# Power_Circuit.net
KiCad netlist of a schematic drawn in Altium Designer
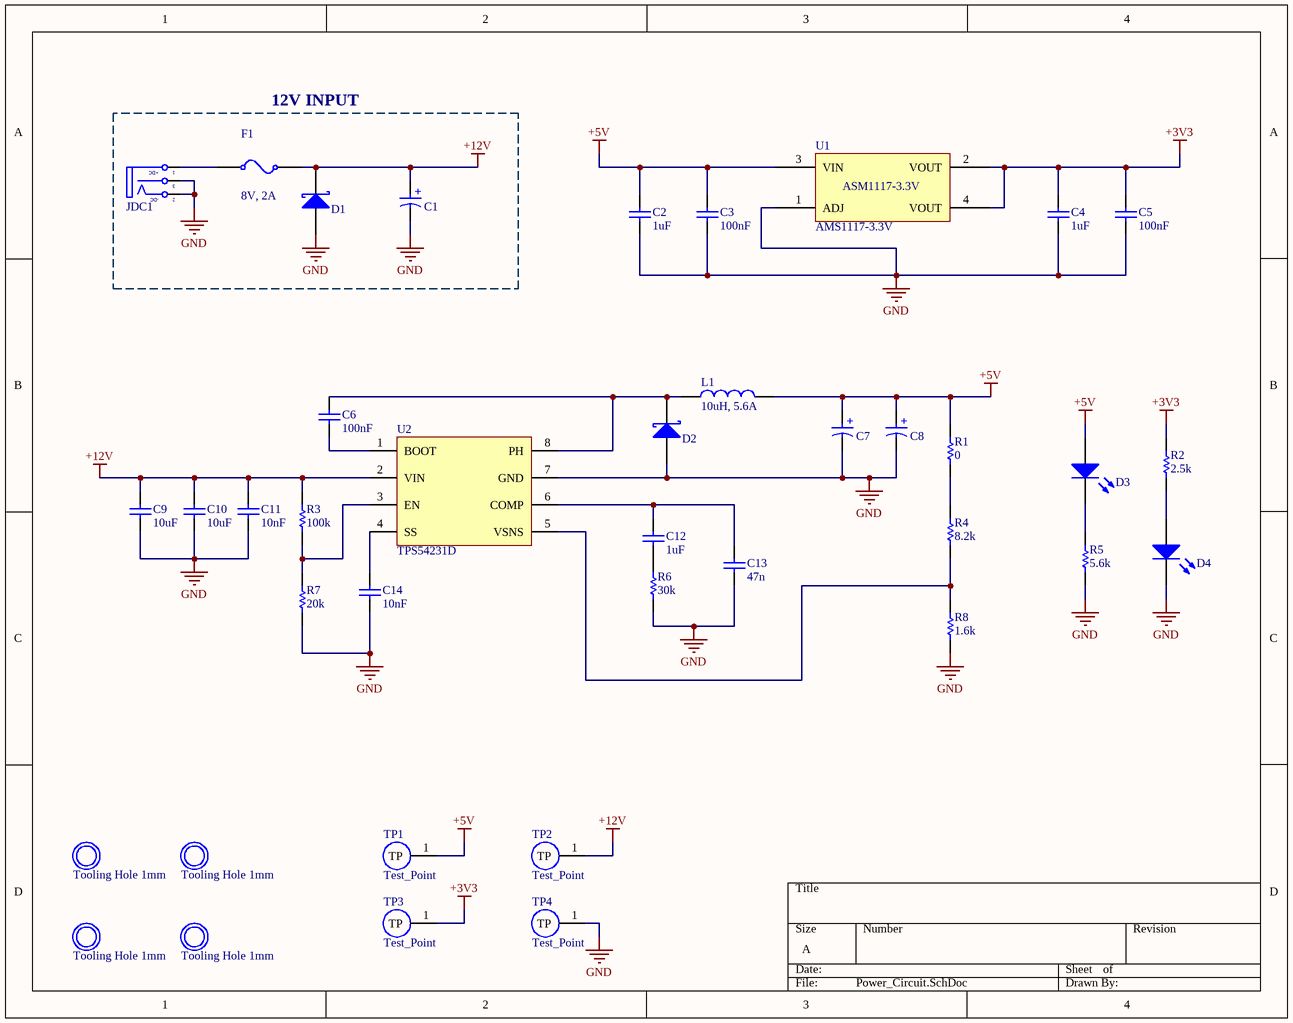
[diagram p0: Power_Circuit.SchDoc]

(export (version "E")
  (design (tool "Eeschema 10.0.6"))
  (components
    (comp (ref "C1")
      (value "47uF")
      (footprint "WCAP-ASLI_D4H5.5")
      (description "V-Chip, D4 x H5.5mm, 22uF, 16V")
      (libsource (lib "SMIOT_Lib_Schematic") (part "865080340003"))
    )
    (comp (ref "C2")
      (value "1uF")
      (footprint "CAP_0603")
      (description "CAP, size 0603, 1uF")
      (libsource (lib "SMIOT_Lib_Schematic") (part "01060310510"))
    )
    (comp (ref "C3")
      (value "100nF")
      (footprint "CAP_0603")
      (description "CAP, size 0603, 100nF")
      (libsource (lib "SMIOT_Lib_Schematic") (part "01060310410"))
    )
    (comp (ref "C4")
      (value "1uF")
      (footprint "CAP_0603")
      (description "CAP, size 0603, 1uF")
      (libsource (lib "SMIOT_Lib_Schematic") (part "01060310510"))
    )
    (comp (ref "C5")
      (value "100nF")
      (footprint "CAP_0603")
      (description "CAP, size 0603, 100nF")
      (libsource (lib "SMIOT_Lib_Schematic") (part "01060310410"))
    )
    (comp (ref "C6")
      (value "100nF")
      (footprint "CAP_0603")
      (description "CAP, size 0603, 100nF")
      (libsource (lib "SMIOT_Lib_Schematic") (part "01060310410"))
    )
    (comp (ref "C7")
      (value "47uF")
      (footprint "WCAP-ASLI_D5H5.5")
      (description "V-Chip, D5 x H5.5mm, 47uF, 16V")
      (libsource (lib "SMIOT_Lib_Schematic") (part "865080342006"))
    )
    (comp (ref "C8")
      (value "47uF")
      (footprint "WCAP-ASLI_D5H5.5")
      (description "V-Chip, D5 x H5.5mm, 47uF, 16V")
      (libsource (lib "SMIOT_Lib_Schematic") (part "865080342006"))
    )
    (comp (ref "C9")
      (value "10uF")
      (footprint "CAP_0603")
      (description "CAP, size 0603,10uF")
      (libsource (lib "SMIOT_Lib_Schematic") (part "01060310010"))
    )
    (comp (ref "C10")
      (value "10uF")
      (footprint "CAP_0603")
      (description "CAP, size 0603,10uF")
      (libsource (lib "SMIOT_Lib_Schematic") (part "01060310010"))
    )
    (comp (ref "C11")
      (value "10nF")
      (footprint "CAP_0603")
      (description "CAP, size 0603, 10nF")
      (libsource (lib "SMIOT_Lib_Schematic") (part "01060310310"))
    )
    (comp (ref "C12")
      (value "1uF")
      (footprint "CAP_0603")
      (description "CAP, size 0603, 1uF")
      (libsource (lib "SMIOT_Lib_Schematic") (part "01060310510"))
    )
    (comp (ref "C13")
      (value "47n")
      (footprint "CAP_0603")
      (description "CAP, size 0603, 47nF")
      (libsource (lib "SMIOT_Lib_Schematic") (part "01060347310"))
    )
    (comp (ref "C14")
      (value "10nF")
      (footprint "CAP_0603")
      (description "CAP, size 0603, 10nF")
      (libsource (lib "SMIOT_Lib_Schematic") (part "01060310310"))
    )
    (comp (ref "D1")
      (value "D Schottky")
      (footprint "SS34")
      (description "Schottky Diode")
      (fields (field (name "PUBLISHER") "Altium Limited"))
      (libsource (lib "Board_C24") (part "D Schottky"))
    )
    (comp (ref "D2")
      (value "D Schottky")
      (footprint "SS34")
      (description "Schottky Diode")
      (fields (field (name "PUBLISHER") "Altium Limited"))
      (libsource (lib "SMIOT_Lib_Schematic") (part "D Schottky"))
    )
    (comp (ref "D3")
      (value "LED SMD")
      (footprint "LED_0805_Blue")
      (description "LED")
      (libsource (lib "SMIOT_Lib_Schematic") (part "LED SMD"))
    )
    (comp (ref "D4")
      (value "LED SMD")
      (footprint "LED_0805_Blue")
      (description "LED")
      (libsource (lib "SMIOT_Lib_Schematic") (part "LED SMD"))
    )
    (comp (ref "F1")
      (value "8V, 2A")
      (footprint "Fuse_SMD_1812")
      (description "Resettable Fuse, Size 1812, 8V, 2A")
      (fields (field (name "MANUFACTURER") "Littelfuse"))
      (libsource (lib "SMIOT_Lib_Schematic") (part "061812200008"))
    )
    (comp (ref "H1")
      (value "Tooling Hole 1mm")
      (footprint "2mm")
      (libsource (lib "SMIOT_Lib_Schematic") (part "Tooling Hole 2mm"))
    )
    (comp (ref "H2")
      (value "Tooling Hole 1mm")
      (footprint "2mm")
      (libsource (lib "SMIOT_Lib_Schematic") (part "Tooling Hole 2mm"))
    )
    (comp (ref "H3")
      (value "Tooling Hole 1mm")
      (footprint "2mm")
      (libsource (lib "SMIOT_Lib_Schematic") (part "Tooling Hole 2mm"))
    )
    (comp (ref "H4")
      (value "Tooling Hole 1mm")
      (footprint "2mm")
      (libsource (lib "SMIOT_Lib_Schematic") (part "Tooling Hole 2mm"))
    )
    (comp (ref "JDC1")
      (value "Jack DC")
      (footprint "DC-IN")
      (description "Jack DC input")
      (libsource (lib "SMIOT_Lib_Schematic") (part "Jack DC"))
    )
    (comp (ref "L1")
      (value "10uH, 5.6A")
      (footprint "WE-PD2A_5848")
      (description "WE-PD2A SMT Power Inductor, size 5848, 10uH, 2.2A")
      (fields
        (field (name "MANUFACTURER PART NUMBER") "78477410")
        (field (name "MANUFACTURER") "Wurth Elektronik")
      )
      (libsource (lib "SMIOT_Lib_Schematic") (part "78477410"))
    )
    (comp (ref "R1")
      (value "0")
      (footprint "resistor_0603")
      (description "RES, 0 Ohm, size 0603, 1%")
      (libsource (lib "SMIOT_Lib_Schematic") (part "0006030001"))
    )
    (comp (ref "R2")
      (value "2.5k")
      (footprint "resistor_0603")
      (description "RES, 2.5K Ohm, size 0603, 5%")
      (libsource (lib "SMIOT_Lib_Schematic") (part "0006032525"))
    )
    (comp (ref "R3")
      (value "100k")
      (footprint "resistor_0603")
      (description "RES, 100k Ohm, size 0603, 1%")
      (libsource (lib "SMIOT_Lib_Schematic") (part "0006031041"))
    )
    (comp (ref "R4")
      (value "8.2k")
      (footprint "resistor_0603")
      (description "RES, 8.2 kOhms, size 0603, 1%")
      (libsource (lib "SMIOT_Lib_Schematic") (part "0006038251"))
    )
    (comp (ref "R5")
      (value "5.6k")
      (footprint "resistor_0603")
      (description "RES, 5.6k Ohm, size 0603, 1%")
      (libsource (lib "SMIOT_Lib_Schematic") (part "0006035621"))
    )
    (comp (ref "R6")
      (value "30k")
      (footprint "resistor_0603")
      (description "RES, 30k Ohm, size 0603, 1%")
      (libsource (lib "SMIOT_Lib_Schematic") (part "0006033205"))
    )
    (comp (ref "R7")
      (value "20k")
      (footprint "resistor_0603")
      (description "RES, 20 kOhms, size 0603, 1%")
      (libsource (lib "SMIOT_Lib_Schematic") (part "0006032031"))
    )
    (comp (ref "R8")
      (value "1.6k")
      (footprint "resistor_0603")
      (description "RES, 1.5 kOhms, size 0603, 1%")
      (libsource (lib "SMIOT_Lib_Schematic") (part "0006031521"))
    )
    (comp (ref "TP1")
      (value "Test_Point")
      (footprint "TP_2MM")
      (description "Test point, 2mm radius")
      (libsource (lib "SMIOT_Lib_Schematic") (part "Test_Point"))
    )
    (comp (ref "TP2")
      (value "Test_Point")
      (footprint "TP_2MM")
      (description "Test point, 2mm radius")
      (libsource (lib "SMIOT_Lib_Schematic") (part "Test_Point"))
    )
    (comp (ref "TP3")
      (value "Test_Point")
      (footprint "TP_2MM")
      (description "Test point, 2mm radius")
      (libsource (lib "SMIOT_Lib_Schematic") (part "Test_Point"))
    )
    (comp (ref "TP4")
      (value "Test_Point")
      (footprint "TP_2MM")
      (description "Test point, 2mm radius")
      (libsource (lib "SMIOT_Lib_Schematic") (part "Test_Point"))
    )
    (comp (ref "U1")
      (value "AMS1117-3.3V")
      (footprint "AMS1117-3.3V SOT223")
      (description "AMS1117-3.3V, OUT 3.3V 1A.")
      (fields (field (name "MANUFACTURER") "AMS"))
      (libsource (lib "SMIOT_Lib_Schematic") (part "AMS1117-3.3V"))
    )
    (comp (ref "U2")
      (value "TPS54231D")
      (footprint "SOIC8")
      (description "Buck Switching Regulator IC Positive Adjustable 0.8V 1 Output 2A 8-SOIC (0.154\", 3.90mm Width)")
      (fields (field (name "MFR") "Texas Instruments"))
      (libsource (lib "SMIOT_Lib_Schematic") (part "TPS54231"))
    )
  )
  (nets
    (net (code "1") (name "+3V3") (class "Default")
      (node (ref "C4") (pin "2") (pinfunction "2_2") (pintype "passive"))
      (node (ref "C5") (pin "2") (pinfunction "2_2") (pintype "passive"))
      (node (ref "R2") (pin "2") (pinfunction "2_2") (pintype "passive"))
      (node (ref "TP3") (pin "1") (pinfunction "TP_1") (pintype "passive"))
      (node (ref "U1") (pin "2") (pinfunction "VOUT_2") (pintype "passive"))
      (node (ref "U1") (pin "4") (pinfunction "VOUT_4") (pintype "power_in"))
    )
    (net (code "2") (name "+5V") (class "Default")
      (node (ref "C2") (pin "2") (pinfunction "2_2") (pintype "passive"))
      (node (ref "C3") (pin "2") (pinfunction "2_2") (pintype "passive"))
      (node (ref "C7") (pin "1") (pinfunction "P_1") (pintype "passive"))
      (node (ref "C8") (pin "1") (pinfunction "P_1") (pintype "passive"))
      (node (ref "D3") (pin "1") (pinfunction "A_1") (pintype "passive"))
      (node (ref "L1") (pin "2") (pinfunction "2_2") (pintype "passive"))
      (node (ref "R1") (pin "2") (pinfunction "2_2") (pintype "passive"))
      (node (ref "TP1") (pin "1") (pinfunction "TP_1") (pintype "passive"))
      (node (ref "U1") (pin "3") (pinfunction "VIN_3") (pintype "passive"))
    )
    (net (code "3") (name "+12V") (class "Default")
      (node (ref "C1") (pin "1") (pinfunction "P_1") (pintype "passive"))
      (node (ref "C10") (pin "2") (pinfunction "2_2") (pintype "passive"))
      (node (ref "C11") (pin "2") (pinfunction "2_2") (pintype "passive"))
      (node (ref "C9") (pin "2") (pinfunction "2_2") (pintype "passive"))
      (node (ref "D1") (pin "2") (pinfunction "K_2") (pintype "passive"))
      (node (ref "F1") (pin "1") (pinfunction "1_1") (pintype "passive"))
      (node (ref "R3") (pin "2") (pinfunction "2_2") (pintype "passive"))
      (node (ref "TP2") (pin "1") (pinfunction "TP_1") (pintype "passive"))
      (node (ref "U2") (pin "2") (pinfunction "VIN_2") (pintype "passive"))
    )
    (net (code "4") (name "GND") (class "Default")
      (node (ref "C1") (pin "2") (pinfunction "N_2") (pintype "passive"))
      (node (ref "C10") (pin "1") (pinfunction "1_1") (pintype "passive"))
      (node (ref "C11") (pin "1") (pinfunction "1_1") (pintype "passive"))
      (node (ref "C13") (pin "1") (pinfunction "1_1") (pintype "passive"))
      (node (ref "C14") (pin "1") (pinfunction "1_1") (pintype "passive"))
      (node (ref "C2") (pin "1") (pinfunction "1_1") (pintype "passive"))
      (node (ref "C3") (pin "1") (pinfunction "1_1") (pintype "passive"))
      (node (ref "C4") (pin "1") (pinfunction "1_1") (pintype "passive"))
      (node (ref "C5") (pin "1") (pinfunction "1_1") (pintype "passive"))
      (node (ref "C7") (pin "2") (pinfunction "N_2") (pintype "passive"))
      (node (ref "C8") (pin "2") (pinfunction "N_2") (pintype "passive"))
      (node (ref "C9") (pin "1") (pinfunction "1_1") (pintype "passive"))
      (node (ref "D1") (pin "1") (pinfunction "A_1") (pintype "passive"))
      (node (ref "D2") (pin "1") (pinfunction "A_1") (pintype "passive"))
      (node (ref "D4") (pin "2") (pinfunction "K_2") (pintype "passive"))
      (node (ref "JDC1") (pin "2") (pinfunction "TN_2") (pintype "passive"))
      (node (ref "JDC1") (pin "3") (pinfunction "S_3") (pintype "power_in"))
      (node (ref "R5") (pin "1") (pinfunction "1_1") (pintype "passive"))
      (node (ref "R6") (pin "1") (pinfunction "1_1") (pintype "passive"))
      (node (ref "R7") (pin "1") (pinfunction "1_1") (pintype "passive"))
      (node (ref "R8") (pin "1") (pinfunction "1_1") (pintype "passive"))
      (node (ref "TP4") (pin "1") (pinfunction "TP_1") (pintype "passive"))
      (node (ref "U1") (pin "1") (pinfunction "ADJ_1") (pintype "power_in"))
      (node (ref "U2") (pin "7") (pinfunction "GND_7") (pintype "passive"))
    )
    (net (code "5") (name "Net-(C12-Pad2)") (class "Default")
      (node (ref "C12") (pin "2") (pinfunction "2_2") (pintype "passive"))
      (node (ref "R6") (pin "2") (pinfunction "2_2") (pintype "passive"))
    )
    (net (code "6") (name "Net-(D2-K)") (class "Default")
      (node (ref "C6") (pin "2") (pinfunction "2_2") (pintype "passive"))
      (node (ref "D2") (pin "2") (pinfunction "K_2") (pintype "passive"))
      (node (ref "L1") (pin "1") (pinfunction "1_1") (pintype "passive"))
      (node (ref "U2") (pin "8") (pinfunction "PH_8") (pintype "passive"))
    )
    (net (code "7") (name "Net-(D3-K)") (class "Default")
      (node (ref "D3") (pin "2") (pinfunction "K_2") (pintype "passive"))
      (node (ref "R5") (pin "2") (pinfunction "2_2") (pintype "passive"))
    )
    (net (code "8") (name "Net-(D4-A)") (class "Default")
      (node (ref "D4") (pin "1") (pinfunction "A_1") (pintype "passive"))
      (node (ref "R2") (pin "1") (pinfunction "1_1") (pintype "passive"))
    )
    (net (code "9") (name "Net-(JDC1-T)") (class "Default")
      (node (ref "F1") (pin "0") (pinfunction "0_0") (pintype "passive"))
      (node (ref "JDC1") (pin "1") (pinfunction "T_1") (pintype "passive"))
    )
    (net (code "10") (name "Net-(R1-Pad1)") (class "Default")
      (node (ref "R1") (pin "1") (pinfunction "1_1") (pintype "passive"))
      (node (ref "R4") (pin "2") (pinfunction "2_2") (pintype "passive"))
    )
    (net (code "11") (name "Net-(U2-BOOT)") (class "Default")
      (node (ref "C6") (pin "1") (pinfunction "1_1") (pintype "passive"))
      (node (ref "U2") (pin "1") (pinfunction "BOOT_1") (pintype "passive"))
    )
    (net (code "12") (name "Net-(U2-COMP)") (class "Default")
      (node (ref "C12") (pin "1") (pinfunction "1_1") (pintype "passive"))
      (node (ref "C13") (pin "2") (pinfunction "2_2") (pintype "passive"))
      (node (ref "U2") (pin "6") (pinfunction "COMP_6") (pintype "passive"))
    )
    (net (code "13") (name "Net-(U2-EN)") (class "Default")
      (node (ref "R3") (pin "1") (pinfunction "1_1") (pintype "passive"))
      (node (ref "R7") (pin "2") (pinfunction "2_2") (pintype "passive"))
      (node (ref "U2") (pin "3") (pinfunction "EN_3") (pintype "passive"))
    )
    (net (code "14") (name "Net-(U2-SS)") (class "Default")
      (node (ref "C14") (pin "2") (pinfunction "2_2") (pintype "passive"))
      (node (ref "U2") (pin "4") (pinfunction "SS_4") (pintype "passive"))
    )
    (net (code "15") (name "Net-(U2-VSNS)") (class "Default")
      (node (ref "R4") (pin "1") (pinfunction "1_1") (pintype "passive"))
      (node (ref "R8") (pin "2") (pinfunction "2_2") (pintype "passive"))
      (node (ref "U2") (pin "5") (pinfunction "VSNS_5") (pintype "passive"))
    )
  )
)
